# Sheet1.net
KiCad netlist of a schematic drawn in Altium Designer
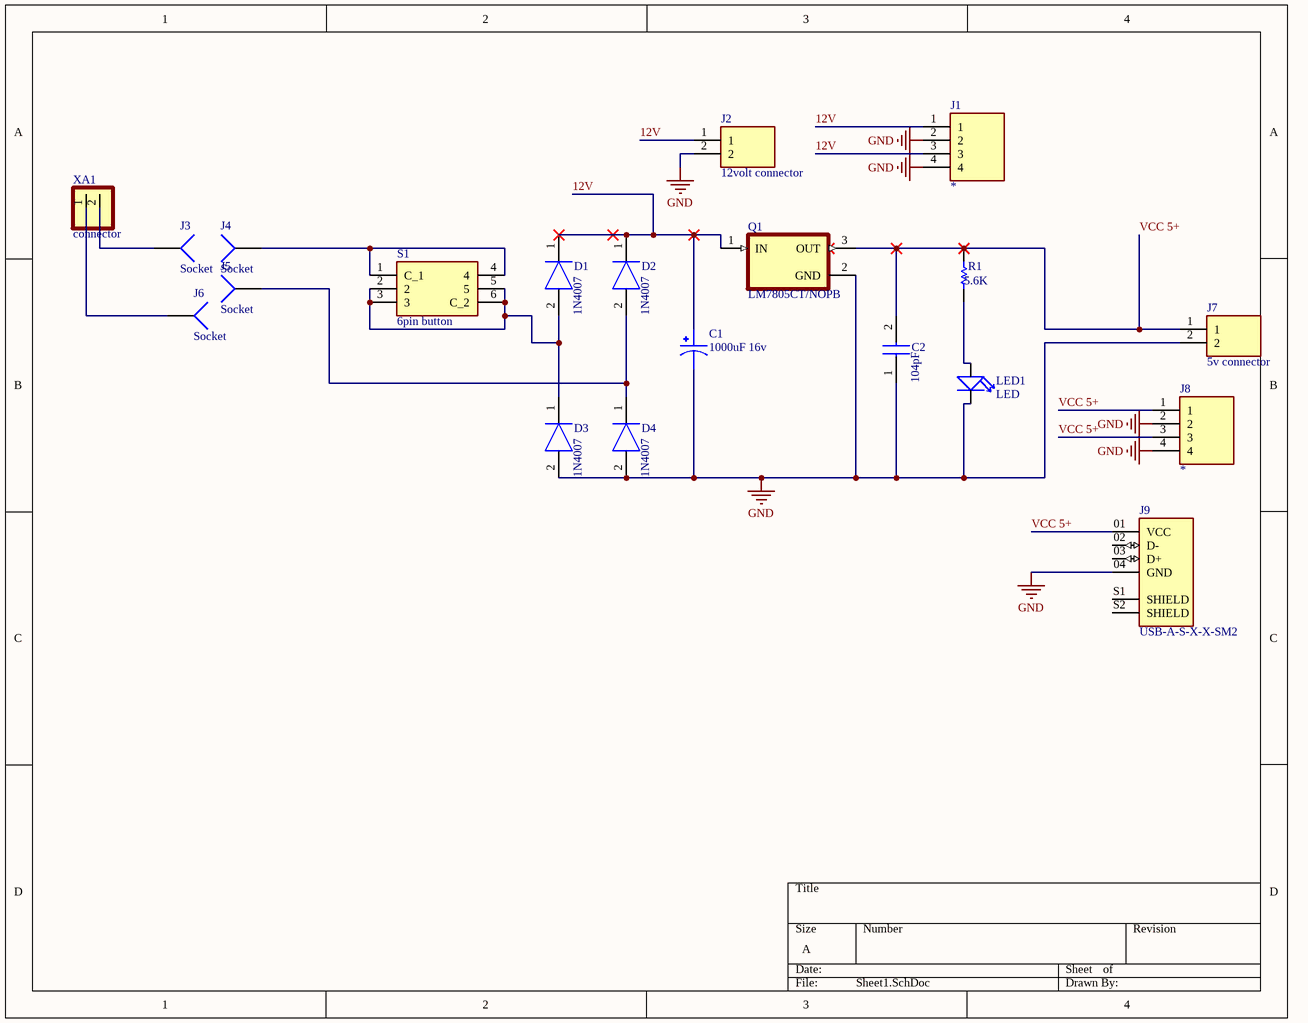
[diagram p0: Sheet1.SchDoc]

(export (version "E")
  (design (tool "Eeschema 10.0.6"))
  (components
    (comp (ref "C1")
      (value "1000uF 16v")
      (footprint "CAPPRD500W60D1330H2700")
      (description "4700ÂµF 10V Aluminum Electrolytic Capacitors Radial, Can 98.8mOhm @ 120Hz 2000 Hrs @ 85Â°C")
      (fields (field (name "MP") "478CKS010M") (field (name "MF") "Illinois Capacitor"))
      (libsource (lib "CAP") (part "478CKS010M"))
    )
    (comp (ref "C2")
      (value "104pF")
      (footprint "SamacSys:B32520C3104K000")
      (description "Capacitor")
      (fields (field (name "MANUFACTURER_PART_NUMBER") "B32520C3104K000"))
      (libsource (lib "nonpolar capacitor square") (part "B32520C3104K000"))
    )
    (comp (ref "D1")
      (value "1N4007")
      (footprint "SamacSys:DIOAD1138W56L406D183")
      (description "Diode")
      (fields (field (name "MANUFACTURER_PART_NUMBER") "1N4678 (DO35)"))
      (libsource (lib "diode with 3d model") (part "1N4678__DO35_"))
    )
    (comp (ref "D2")
      (value "1N4007")
      (footprint "SamacSys:DIOAD1138W56L406D183")
      (description "Diode")
      (fields (field (name "MANUFACTURER_PART_NUMBER") "1N4678 (DO35)"))
      (libsource (lib "diode with 3d model") (part "1N4678__DO35_"))
    )
    (comp (ref "D3")
      (value "1N4007")
      (footprint "SamacSys:DIOAD1138W56L406D183")
      (description "Diode")
      (fields (field (name "MANUFACTURER_PART_NUMBER") "1N4678 (DO35)"))
      (libsource (lib "diode with 3d model") (part "1N4678__DO35_"))
    )
    (comp (ref "D4")
      (value "1N4007")
      (footprint "SamacSys:DIOAD1138W56L406D183")
      (description "Diode")
      (fields (field (name "MANUFACTURER_PART_NUMBER") "1N4678 (DO35)"))
      (libsource (lib "diode with 3d model") (part "1N4678__DO35_"))
    )
    (comp (ref "J1")
      (value "282825-4")
      (footprint "TE_282825-4")
      (fields (field (name "MF") "TE Connectivity") (field (name "COMMENT_1") "*"))
      (libsource (lib "4pin creamshell 3D") (part "282825-4"))
    )
    (comp (ref "J2")
      (value "12volt connector")
      (footprint "JST_B2B-XH-A(LF)(SN)")
      (description "Connector Header Through Hole 2 position 0.098 _2.50mm_")
      (fields (field (name "MP") "B2B-XH-A_LF__SN_") (field (name "MF") "JST Sales"))
      (libsource (lib "2pin connector 3D") (part "B2B-XH-A(LF)(SN)"))
    )
    (comp (ref "J3")
      (value "Socket")
      (footprint "PIN1")
      (fields (field (name "PUBLISHER") "Altium Limited"))
      (libsource (lib "Miscellaneous Connectors") (part "Socket"))
    )
    (comp (ref "J4")
      (value "Socket")
      (footprint "PIN1")
      (fields (field (name "PUBLISHER") "Altium Limited"))
      (libsource (lib "Miscellaneous Connectors") (part "Socket"))
    )
    (comp (ref "J5")
      (value "Socket")
      (footprint "PIN1")
      (fields (field (name "PUBLISHER") "Altium Limited"))
      (libsource (lib "Miscellaneous Connectors") (part "Socket"))
    )
    (comp (ref "J6")
      (value "Socket")
      (footprint "PIN1")
      (fields (field (name "PUBLISHER") "Altium Limited"))
      (libsource (lib "Miscellaneous Connectors") (part "Socket"))
    )
    (comp (ref "J7")
      (value "5v connector")
      (footprint "JST_B2B-XH-A(LF)(SN)")
      (description "Connector Header Through Hole 2 position 0.098 _2.50mm_")
      (fields (field (name "MP") "B2B-XH-A_LF__SN_") (field (name "MF") "JST Sales"))
      (libsource (lib "2pin connector 3D") (part "B2B-XH-A(LF)(SN)"))
    )
    (comp (ref "J8")
      (value "282825-4")
      (footprint "TE_282825-4")
      (fields (field (name "MF") "TE Connectivity") (field (name "COMMENT_1") "*"))
      (libsource (lib "4pin creamshell 3D") (part "282825-4"))
    )
    (comp (ref "J9")
      (value "USB-A-S-X-X-SM2")
      (footprint "SAMTEC_USB-A-S-X-X-SM2")
      (description "USB-A (USB TYPE-A) USB 2.0 Receptacle Connector 4 Position Surface Mount, Right Angle")
      (fields (field (name "MP") "USB-A-S-F-B-SM2") (field (name "MF") "Samtec"))
      (libsource (lib "usb 3d") (part "USB-A-S-X-X-SM2"))
    )
    (comp (ref "LED1")
      (value "LED")
      (footprint "LED2-2.54-D10MM")
      (description "DIP LED Green-Vaporous Green-10mm")
      (fields (field (name "MF") "Chengguangxing") (field (name "MP") "G1004DC"))
      (libsource (lib "LED 3D") (part "DIP-LED-GREEN-VAPOROUS-GREEN-10MM(2P-D10MM)"))
    )
    (comp (ref "Q1")
      (value "LM7805CT/NOPB")
      (footprint "TO254P1054X470X2600-3")
      (description "Linear Voltage Regulator IC 1 Output 1A TO-220-3")
      (fields (field (name "MP") "LM7805CT") (field (name "MF") "ON Semiconductor"))
      (libsource (lib "LM7805 3D") (part "LM7805CT/NOPB"))
    )
    (comp (ref "R1")
      (value "5.6K")
      (footprint "AXIAL-0.5")
      (description "Semiconductor Resistor")
      (fields (field (name "PUBLISHER") "Altium Limited"))
      (libsource (lib "Miscellaneous Devices") (part "Res Semi"))
    )
    (comp (ref "S1")
      (value "6pin button")
      (footprint "SamacSys:MPSA22E080150")
      (description "Switch")
      (fields (field (name "MANUFACTURER_PART_NUMBER") "MPSA-22E08-0150"))
      (libsource (lib "6pin push button") (part "MPSA-22E08-0150"))
    )
    (comp (ref "XA1")
      (value "connector")
      (footprint "PHOENIX_MKDS1/2-3.81")
      (description "2 Position Wire to Board Terminal Block Horizontal with Board 0.150 _3.81mm_ Through Hole")
      (fields (field (name "MF") "Phoenix Contact") (field (name "MP") "MKDS 1/ 2-3.81"))
      (libsource (lib "connector 2 pin 3D") (part "MKDS1/2-3.81"))
    )
  )
  (nets
    (net (code "1") (name "/12V") (class "Default")
      (node (ref "C1") (pin "1") (pinfunction "1_1") (pintype "passive"))
      (node (ref "D1") (pin "1") (pinfunction "K_1") (pintype "passive"))
      (node (ref "D2") (pin "1") (pinfunction "K_1") (pintype "passive"))
      (node (ref "J1") (pin "1") (pinfunction "1_1") (pintype "passive"))
      (node (ref "J1") (pin "3") (pinfunction "3_3") (pintype "passive"))
      (node (ref "J2") (pin "1") (pinfunction "1_1") (pintype "passive"))
      (node (ref "Q1") (pin "1") (pinfunction "IN_1") (pintype "input"))
    )
    (net (code "2") (name "/VCC 5+") (class "Default")
      (node (ref "C2") (pin "2") (pinfunction "2_2") (pintype "passive"))
      (node (ref "J7") (pin "1") (pinfunction "1_1") (pintype "passive"))
      (node (ref "J8") (pin "1") (pinfunction "1_1") (pintype "passive"))
      (node (ref "J8") (pin "3") (pinfunction "3_3") (pintype "passive"))
      (node (ref "J9") (pin "01") (pinfunction "VCC_01") (pintype "power_in"))
      (node (ref "Q1") (pin "3") (pinfunction "OUT_3") (pintype "output"))
      (node (ref "R1") (pin "2") (pinfunction "2_2") (pintype "passive"))
    )
    (net (code "3") (name "GND") (class "Default")
      (node (ref "C1") (pin "2") (pinfunction "2_2") (pintype "passive"))
      (node (ref "C2") (pin "1") (pinfunction "1_1") (pintype "passive"))
      (node (ref "D3") (pin "2") (pinfunction "A_2") (pintype "passive"))
      (node (ref "D4") (pin "2") (pinfunction "A_2") (pintype "passive"))
      (node (ref "J1") (pin "2") (pinfunction "2_2") (pintype "passive"))
      (node (ref "J1") (pin "4") (pinfunction "4_4") (pintype "passive"))
      (node (ref "J2") (pin "2") (pinfunction "2_2") (pintype "passive"))
      (node (ref "J7") (pin "2") (pinfunction "2_2") (pintype "passive"))
      (node (ref "J8") (pin "2") (pinfunction "2_2") (pintype "passive"))
      (node (ref "J8") (pin "4") (pinfunction "4_4") (pintype "passive"))
      (node (ref "J9") (pin "04") (pinfunction "GND_04") (pintype "power_in"))
      (node (ref "LED1") (pin "NEG") (pinfunction "NEG_NEG") (pintype "passive"))
      (node (ref "Q1") (pin "2") (pinfunction "GND_2") (pintype "power_in"))
    )
    (net (code "4") (name "Net-(D1-A)") (class "Default")
      (node (ref "D1") (pin "2") (pinfunction "A_2") (pintype "passive"))
      (node (ref "D3") (pin "1") (pinfunction "K_1") (pintype "passive"))
      (node (ref "S1") (pin "2") (pinfunction "2_2") (pintype "passive"))
      (node (ref "S1") (pin "3") (pinfunction "3_3") (pintype "passive"))
      (node (ref "S1") (pin "5") (pinfunction "5_5") (pintype "passive"))
      (node (ref "S1") (pin "6") (pinfunction "C_2_6") (pintype "passive"))
    )
    (net (code "5") (name "Net-(D2-A)") (class "Default")
      (node (ref "D2") (pin "2") (pinfunction "A_2") (pintype "passive"))
      (node (ref "D4") (pin "1") (pinfunction "K_1") (pintype "passive"))
      (node (ref "J5") (pin "1") (pinfunction "1_1") (pintype "passive"))
    )
    (net (code "6") (name "Net-(J3-Pad1)") (class "Default")
      (node (ref "J3") (pin "1") (pinfunction "1_1") (pintype "passive"))
      (node (ref "XA1") (pin "2") (pinfunction "2_2") (pintype "passive"))
    )
    (net (code "7") (name "Net-(J6-Pad1)") (class "Default")
      (node (ref "J6") (pin "1") (pinfunction "1_1") (pintype "passive"))
      (node (ref "XA1") (pin "1") (pinfunction "1_1") (pintype "passive"))
    )
    (net (code "8") (name "Net-(LED1-PadPOS)") (class "Default")
      (node (ref "LED1") (pin "POS") (pinfunction "POS_POS") (pintype "passive"))
      (node (ref "R1") (pin "1") (pinfunction "1_1") (pintype "passive"))
    )
    (net (code "9") (name "Net-(S1-C_1)") (class "Default")
      (node (ref "J4") (pin "1") (pinfunction "1_1") (pintype "passive"))
      (node (ref "S1") (pin "1") (pinfunction "C_1_1") (pintype "passive"))
      (node (ref "S1") (pin "4") (pinfunction "4_4") (pintype "passive"))
    )
    (net (code "10") (name "unconnected-(J9-D+-Pad03)") (class "Default")
      (node (ref "J9") (pin "03") (pinfunction "D+_03") (pintype "bidirectional"))
    )
    (net (code "11") (name "unconnected-(J9-D--Pad02)") (class "Default")
      (node (ref "J9") (pin "02") (pinfunction "D-_02") (pintype "bidirectional"))
    )
    (net (code "12") (name "unconnected-(J9-SHIELD-PadS1)") (class "Default")
      (node (ref "J9") (pin "S1") (pinfunction "SHIELD_S1") (pintype "passive"))
    )
    (net (code "13") (name "unconnected-(J9-SHIELD-PadS2)") (class "Default")
      (node (ref "J9") (pin "S2") (pinfunction "SHIELD_S2") (pintype "passive"))
    )
  )
)
